# AD7173adcModule.net
KiCad netlist of a schematic drawn in Altium Designer
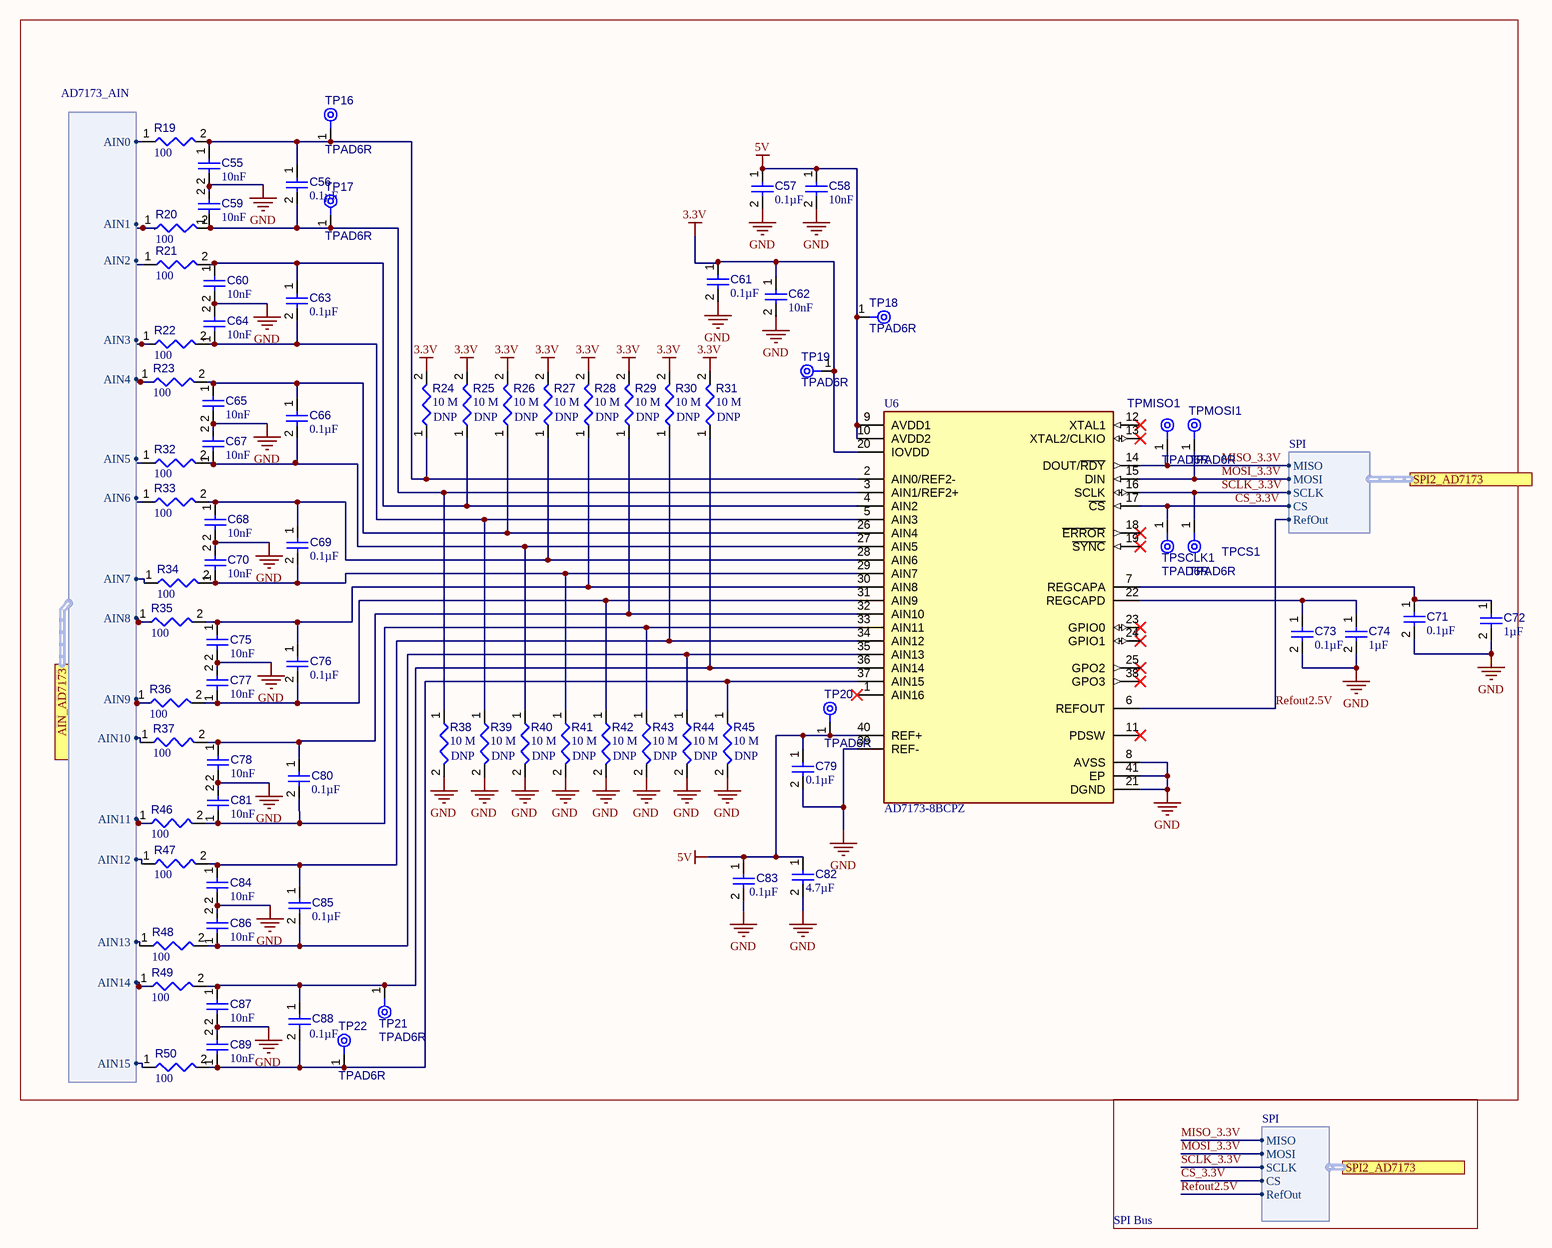
[diagram p0: AD7173adcModule.SchDoc]

(export (version "E")
  (design (tool "Eeschema 10.0.6"))
  (components
    (comp (ref "C55")
      (value "10nF")
      (footprint "CAPC1608X90X40NL10T20")
      (description "Chip Capacitor, 100 nF, +/- 10%, 50 V, 0603 (1608 Metric)")
      (fields (field (name "TOLERANCE") "10%") (field (name "Comment") "Capacitor 100 nF +/-10% 50 V 0603"))
      (libsource (lib "Gidon_Workspace") (part "CAP-NP-2"))
    )
    (comp (ref "C56")
      (value "0.1µF")
      (footprint "CAPC1608X90X40LL10T20")
      (description "Chip Capacitor, 1 uF, +/- 10%, 25 V, 0603 (1608 Metric)")
      (fields (field (name "TOLERANCE") "10%") (field (name "Comment") "Capacitor 1 uF +/- 10% 25 V 0603"))
      (libsource (lib "Gidon_Workspace") (part "CAP-NP-2"))
    )
    (comp (ref "C57")
      (value "0.1µF")
      (footprint "CAPC1608X90X40LL10T20")
      (description "Chip Capacitor, 1 uF, +/- 10%, 25 V, 0603 (1608 Metric)")
      (fields (field (name "TOLERANCE") "10%") (field (name "Comment") "Capacitor 1 uF +/- 10% 25 V 0603"))
      (libsource (lib "Gidon_Workspace") (part "CAP-NP-2"))
    )
    (comp (ref "C58")
      (value "10nF")
      (footprint "CAPC1608X90X40NL10T20")
      (description "Chip Capacitor, 100 nF, +/- 10%, 50 V, 0603 (1608 Metric)")
      (fields (field (name "TOLERANCE") "10%") (field (name "Comment") "Capacitor 100 nF +/-10% 50 V 0603"))
      (libsource (lib "Gidon_Workspace") (part "CAP-NP-2"))
    )
    (comp (ref "C59")
      (value "10nF")
      (footprint "CAPC1608X90X40NL10T20")
      (description "Chip Capacitor, 100 nF, +/- 10%, 50 V, 0603 (1608 Metric)")
      (fields (field (name "TOLERANCE") "10%") (field (name "Comment") "Capacitor 100 nF +/-10% 50 V 0603"))
      (libsource (lib "Gidon_Workspace") (part "CAP-NP-2"))
    )
    (comp (ref "C60")
      (value "10nF")
      (footprint "CAPC1608X90X40NL10T20")
      (description "Chip Capacitor, 100 nF, +/- 10%, 50 V, 0603 (1608 Metric)")
      (fields (field (name "TOLERANCE") "10%") (field (name "Comment") "Capacitor 100 nF +/-10% 50 V 0603"))
      (libsource (lib "Gidon_Workspace") (part "CAP-NP-2"))
    )
    (comp (ref "C61")
      (value "0.1µF")
      (footprint "CAPC1608X90X40LL10T20")
      (description "Chip Capacitor, 1 uF, +/- 10%, 25 V, 0603 (1608 Metric)")
      (fields (field (name "TOLERANCE") "10%") (field (name "Comment") "Capacitor 1 uF +/- 10% 25 V 0603"))
      (libsource (lib "Gidon_Workspace") (part "CAP-NP-2"))
    )
    (comp (ref "C62")
      (value "10nF")
      (footprint "CAPC1608X90X40NL10T20")
      (description "Chip Capacitor, 100 nF, +/- 10%, 50 V, 0603 (1608 Metric)")
      (fields (field (name "TOLERANCE") "10%") (field (name "Comment") "Capacitor 100 nF +/-10% 50 V 0603"))
      (libsource (lib "Gidon_Workspace") (part "CAP-NP-2"))
    )
    (comp (ref "C63")
      (value "0.1µF")
      (footprint "CAPC1608X90X40LL10T20")
      (description "Chip Capacitor, 1 uF, +/- 10%, 25 V, 0603 (1608 Metric)")
      (fields (field (name "TOLERANCE") "10%") (field (name "Comment") "Capacitor 1 uF +/- 10% 25 V 0603"))
      (libsource (lib "Gidon_Workspace") (part "CAP-NP-2"))
    )
    (comp (ref "C64")
      (value "10nF")
      (footprint "CAPC1608X90X40NL10T20")
      (description "Chip Capacitor, 100 nF, +/- 10%, 50 V, 0603 (1608 Metric)")
      (fields (field (name "TOLERANCE") "10%") (field (name "Comment") "Capacitor 100 nF +/-10% 50 V 0603"))
      (libsource (lib "Gidon_Workspace") (part "CAP-NP-2"))
    )
    (comp (ref "C65")
      (value "10nF")
      (footprint "CAPC1608X90X40NL10T20")
      (description "Chip Capacitor, 100 nF, +/- 10%, 50 V, 0603 (1608 Metric)")
      (fields (field (name "TOLERANCE") "10%") (field (name "Comment") "Capacitor 100 nF +/-10% 50 V 0603"))
      (libsource (lib "Gidon_Workspace") (part "CAP-NP-2"))
    )
    (comp (ref "C66")
      (value "0.1µF")
      (footprint "CAPC1608X90X40LL10T20")
      (description "Chip Capacitor, 1 uF, +/- 10%, 25 V, 0603 (1608 Metric)")
      (fields (field (name "TOLERANCE") "10%") (field (name "Comment") "Capacitor 1 uF +/- 10% 25 V 0603"))
      (libsource (lib "Gidon_Workspace") (part "CAP-NP-2"))
    )
    (comp (ref "C67")
      (value "10nF")
      (footprint "CAPC1608X90X40NL10T20")
      (description "Chip Capacitor, 100 nF, +/- 10%, 50 V, 0603 (1608 Metric)")
      (fields (field (name "TOLERANCE") "10%") (field (name "Comment") "Capacitor 100 nF +/-10% 50 V 0603"))
      (libsource (lib "Gidon_Workspace") (part "CAP-NP-2"))
    )
    (comp (ref "C68")
      (value "10nF")
      (footprint "CAPC1608X90X40NL10T20")
      (description "Chip Capacitor, 100 nF, +/- 10%, 50 V, 0603 (1608 Metric)")
      (fields (field (name "TOLERANCE") "10%") (field (name "Comment") "Capacitor 100 nF +/-10% 50 V 0603"))
      (libsource (lib "Gidon_Workspace") (part "CAP-NP-2"))
    )
    (comp (ref "C69")
      (value "0.1µF")
      (footprint "CAPC1608X90X40LL10T20")
      (description "Chip Capacitor, 1 uF, +/- 10%, 25 V, 0603 (1608 Metric)")
      (fields (field (name "TOLERANCE") "10%") (field (name "Comment") "Capacitor 1 uF +/- 10% 25 V 0603"))
      (libsource (lib "Gidon_Workspace") (part "CAP-NP-2"))
    )
    (comp (ref "C70")
      (value "10nF")
      (footprint "CAPC1608X90X40NL10T20")
      (description "Chip Capacitor, 100 nF, +/- 10%, 50 V, 0603 (1608 Metric)")
      (fields (field (name "TOLERANCE") "10%") (field (name "Comment") "Capacitor 100 nF +/-10% 50 V 0603"))
      (libsource (lib "Gidon_Workspace") (part "CAP-NP-2"))
    )
    (comp (ref "C71")
      (value "0.1µF")
      (footprint "CAPC1608X90X40LL10T20")
      (description "Chip Capacitor, 1 uF, +/- 10%, 25 V, 0603 (1608 Metric)")
      (fields (field (name "TOLERANCE") "10%") (field (name "Comment") "Capacitor 1 uF +/- 10% 25 V 0603"))
      (libsource (lib "Gidon_Workspace") (part "CAP-NP-2"))
    )
    (comp (ref "C72")
      (value "1µF")
      (footprint "CAPC1608X94X35NL15T15")
      (description "Chip Capacitor, 1 uF, +/- 10%, 16 V, 0603 (1608 Metric)")
      (fields (field (name "TOLERANCE") "10%") (field (name "Comment") "Capacitor 1 uF +/- 10% 16 V 0603"))
      (libsource (lib "Gidon_Workspace") (part "CAP-NP-2"))
    )
    (comp (ref "C73")
      (value "0.1µF")
      (footprint "CAPC1608X90X40LL10T20")
      (description "Chip Capacitor, 1 uF, +/- 10%, 25 V, 0603 (1608 Metric)")
      (fields (field (name "TOLERANCE") "10%") (field (name "Comment") "Capacitor 1 uF +/- 10% 25 V 0603"))
      (libsource (lib "Gidon_Workspace") (part "CAP-NP-2"))
    )
    (comp (ref "C74")
      (value "1µF")
      (footprint "CAPC1608X94X35NL15T15")
      (description "Chip Capacitor, 1 uF, +/- 10%, 16 V, 0603 (1608 Metric)")
      (fields (field (name "TOLERANCE") "10%") (field (name "Comment") "Capacitor 1 uF +/- 10% 16 V 0603"))
      (libsource (lib "Gidon_Workspace") (part "CAP-NP-2"))
    )
    (comp (ref "C75")
      (value "10nF")
      (footprint "CAPC1608X90X40NL10T20")
      (description "Chip Capacitor, 100 nF, +/- 10%, 50 V, 0603 (1608 Metric)")
      (fields (field (name "TOLERANCE") "10%") (field (name "Comment") "Capacitor 100 nF +/-10% 50 V 0603"))
      (libsource (lib "Gidon_Workspace") (part "CAP-NP-2"))
    )
    (comp (ref "C76")
      (value "0.1µF")
      (footprint "CAPC1608X90X40LL10T20")
      (description "Chip Capacitor, 1 uF, +/- 10%, 25 V, 0603 (1608 Metric)")
      (fields (field (name "TOLERANCE") "10%") (field (name "Comment") "Capacitor 1 uF +/- 10% 25 V 0603"))
      (libsource (lib "Gidon_Workspace") (part "CAP-NP-2"))
    )
    (comp (ref "C77")
      (value "10nF")
      (footprint "CAPC1608X90X40NL10T20")
      (description "Chip Capacitor, 100 nF, +/- 10%, 50 V, 0603 (1608 Metric)")
      (fields (field (name "TOLERANCE") "10%") (field (name "Comment") "Capacitor 100 nF +/-10% 50 V 0603"))
      (libsource (lib "Gidon_Workspace") (part "CAP-NP-2"))
    )
    (comp (ref "C78")
      (value "10nF")
      (footprint "CAPC1608X90X40NL10T20")
      (description "Chip Capacitor, 100 nF, +/- 10%, 50 V, 0603 (1608 Metric)")
      (fields (field (name "TOLERANCE") "10%") (field (name "Comment") "Capacitor 100 nF +/-10% 50 V 0603"))
      (libsource (lib "Gidon_Workspace") (part "CAP-NP-2"))
    )
    (comp (ref "C79")
      (value "0.1µF")
      (footprint "CAPC1608X90X40LL10T20")
      (description "Chip Capacitor, 1 uF, +/- 10%, 25 V, 0603 (1608 Metric)")
      (fields (field (name "TOLERANCE") "10%") (field (name "Comment") "Capacitor 1 uF +/- 10% 25 V 0603"))
      (libsource (lib "Gidon_Workspace") (part "CAP-NP-2"))
    )
    (comp (ref "C80")
      (value "0.1µF")
      (footprint "CAPC1608X90X40LL10T20")
      (description "Chip Capacitor, 1 uF, +/- 10%, 25 V, 0603 (1608 Metric)")
      (fields (field (name "TOLERANCE") "10%") (field (name "Comment") "Capacitor 1 uF +/- 10% 25 V 0603"))
      (libsource (lib "Gidon_Workspace") (part "CAP-NP-2"))
    )
    (comp (ref "C81")
      (value "10nF")
      (footprint "CAPC1608X90X40NL10T20")
      (description "Chip Capacitor, 100 nF, +/- 10%, 50 V, 0603 (1608 Metric)")
      (fields (field (name "TOLERANCE") "10%") (field (name "Comment") "Capacitor 100 nF +/-10% 50 V 0603"))
      (libsource (lib "Gidon_Workspace") (part "CAP-NP-2"))
    )
    (comp (ref "C82")
      (value "4.7µF")
      (footprint "CAPC0603(1608)100_L")
      (description "Chip Capacitor, 4.7µF +/-20%, 10V, 0603, Thickness 1 mm")
      (fields (field (name "TOLERANCE") "10%") (field (name "Comment") "Capacitor 4.7µF +/-20% 10V 0603"))
      (libsource (lib "Gidon_Workspace") (part "CAP-NP-2"))
    )
    (comp (ref "C83")
      (value "0.1µF")
      (footprint "CAPC1608X90X40LL10T20")
      (description "Chip Capacitor, 1 uF, +/- 10%, 25 V, 0603 (1608 Metric)")
      (fields (field (name "TOLERANCE") "10%") (field (name "Comment") "Capacitor 1 uF +/- 10% 25 V 0603"))
      (libsource (lib "Gidon_Workspace") (part "CAP-NP-2"))
    )
    (comp (ref "C84")
      (value "10nF")
      (footprint "CAPC1608X90X40NL10T20")
      (description "Chip Capacitor, 100 nF, +/- 10%, 50 V, 0603 (1608 Metric)")
      (fields (field (name "TOLERANCE") "10%") (field (name "Comment") "Capacitor 100 nF +/-10% 50 V 0603"))
      (libsource (lib "Gidon_Workspace") (part "CAP-NP-2"))
    )
    (comp (ref "C85")
      (value "0.1µF")
      (footprint "CAPC1608X90X40LL10T20")
      (description "Chip Capacitor, 1 uF, +/- 10%, 25 V, 0603 (1608 Metric)")
      (fields (field (name "TOLERANCE") "10%") (field (name "Comment") "Capacitor 1 uF +/- 10% 25 V 0603"))
      (libsource (lib "Gidon_Workspace") (part "CAP-NP-2"))
    )
    (comp (ref "C86")
      (value "10nF")
      (footprint "CAPC1608X90X40NL10T20")
      (description "Chip Capacitor, 100 nF, +/- 10%, 50 V, 0603 (1608 Metric)")
      (fields (field (name "TOLERANCE") "10%") (field (name "Comment") "Capacitor 100 nF +/-10% 50 V 0603"))
      (libsource (lib "Gidon_Workspace") (part "CAP-NP-2"))
    )
    (comp (ref "C87")
      (value "10nF")
      (footprint "CAPC1608X90X40NL10T20")
      (description "Chip Capacitor, 100 nF, +/- 10%, 50 V, 0603 (1608 Metric)")
      (fields (field (name "TOLERANCE") "10%") (field (name "Comment") "Capacitor 100 nF +/-10% 50 V 0603"))
      (libsource (lib "Gidon_Workspace") (part "CAP-NP-2"))
    )
    (comp (ref "C88")
      (value "0.1µF")
      (footprint "CAPC1608X90X40LL10T20")
      (description "Chip Capacitor, 1 uF, +/- 10%, 25 V, 0603 (1608 Metric)")
      (fields (field (name "TOLERANCE") "10%") (field (name "Comment") "Capacitor 1 uF +/- 10% 25 V 0603"))
      (libsource (lib "Gidon_Workspace") (part "CAP-NP-2"))
    )
    (comp (ref "C89")
      (value "10nF")
      (footprint "CAPC1608X90X40NL10T20")
      (description "Chip Capacitor, 100 nF, +/- 10%, 50 V, 0603 (1608 Metric)")
      (fields (field (name "TOLERANCE") "10%") (field (name "Comment") "Capacitor 100 nF +/-10% 50 V 0603"))
      (libsource (lib "Gidon_Workspace") (part "CAP-NP-2"))
    )
    (comp (ref "R19")
      (value "100")
      (footprint "RESC0603(1608)_L")
      (description "Chip Resistor, 120 Ohms, +/-5 %, 0.1 W, -55 to 155 degC, 0603")
      (fields (field (name "POWER") "100mW") (field (name "TOLERANCE") "5%"))
      (libsource (lib "Gidon_Workspace") (part "RES-2"))
    )
    (comp (ref "R20")
      (value "100")
      (footprint "RESC0603(1608)_L")
      (description "Chip Resistor, 120 Ohms, +/-5 %, 0.1 W, -55 to 155 degC, 0603")
      (fields (field (name "POWER") "100mW") (field (name "TOLERANCE") "5%"))
      (libsource (lib "Gidon_Workspace") (part "RES-2"))
    )
    (comp (ref "R21")
      (value "100")
      (footprint "RESC0603(1608)_L")
      (description "Chip Resistor, 120 Ohms, +/-5 %, 0.1 W, -55 to 155 degC, 0603")
      (fields (field (name "POWER") "100mW") (field (name "TOLERANCE") "5%"))
      (libsource (lib "Gidon_Workspace") (part "RES-2"))
    )
    (comp (ref "R22")
      (value "100")
      (footprint "RESC0603(1608)_L")
      (description "Chip Resistor, 120 Ohms, +/-5 %, 0.1 W, -55 to 155 degC, 0603")
      (fields (field (name "POWER") "100mW") (field (name "TOLERANCE") "5%"))
      (libsource (lib "Gidon_Workspace") (part "RES-2"))
    )
    (comp (ref "R23")
      (value "100")
      (footprint "RESC0603(1608)_L")
      (description "Chip Resistor, 120 Ohms, +/-5 %, 0.1 W, -55 to 155 degC, 0603")
      (fields (field (name "POWER") "100mW") (field (name "TOLERANCE") "5%"))
      (libsource (lib "Gidon_Workspace") (part "RES-2"))
    )
    (comp (ref "R24")
      (value "10 M")
      (footprint "RESC0603(1608)_L")
      (description "Chip Resistor, 120 Ohms, +/-5 %, 0.1 W, -55 to 155 degC, 0603")
      (fields (field (name "POWER") "100mW") (field (name "TOLERANCE") "5%"))
      (libsource (lib "Gidon_Workspace") (part "RES-2"))
    )
    (comp (ref "R25")
      (value "10 M")
      (footprint "RESC0603(1608)_L")
      (description "Chip Resistor, 120 Ohms, +/-5 %, 0.1 W, -55 to 155 degC, 0603")
      (fields (field (name "POWER") "100mW") (field (name "TOLERANCE") "5%"))
      (libsource (lib "Gidon_Workspace") (part "RES-2"))
    )
    (comp (ref "R26")
      (value "10 M")
      (footprint "RESC0603(1608)_L")
      (description "Chip Resistor, 120 Ohms, +/-5 %, 0.1 W, -55 to 155 degC, 0603")
      (fields (field (name "POWER") "100mW") (field (name "TOLERANCE") "5%"))
      (libsource (lib "Gidon_Workspace") (part "RES-2"))
    )
    (comp (ref "R27")
      (value "10 M")
      (footprint "RESC0603(1608)_L")
      (description "Chip Resistor, 120 Ohms, +/-5 %, 0.1 W, -55 to 155 degC, 0603")
      (fields (field (name "POWER") "100mW") (field (name "TOLERANCE") "5%"))
      (libsource (lib "Gidon_Workspace") (part "RES-2"))
    )
    (comp (ref "R28")
      (value "10 M")
      (footprint "RESC0603(1608)_L")
      (description "Chip Resistor, 120 Ohms, +/-5 %, 0.1 W, -55 to 155 degC, 0603")
      (fields (field (name "POWER") "100mW") (field (name "TOLERANCE") "5%"))
      (libsource (lib "Gidon_Workspace") (part "RES-2"))
    )
    (comp (ref "R29")
      (value "10 M")
      (footprint "RESC0603(1608)_L")
      (description "Chip Resistor, 120 Ohms, +/-5 %, 0.1 W, -55 to 155 degC, 0603")
      (fields (field (name "POWER") "100mW") (field (name "TOLERANCE") "5%"))
      (libsource (lib "Gidon_Workspace") (part "RES-2"))
    )
    (comp (ref "R30")
      (value "10 M")
      (footprint "RESC0603(1608)_L")
      (description "Chip Resistor, 120 Ohms, +/-5 %, 0.1 W, -55 to 155 degC, 0603")
      (fields (field (name "POWER") "100mW") (field (name "TOLERANCE") "5%"))
      (libsource (lib "Gidon_Workspace") (part "RES-2"))
    )
    (comp (ref "R31")
      (value "10 M")
      (footprint "RESC0603(1608)_L")
      (description "Chip Resistor, 120 Ohms, +/-5 %, 0.1 W, -55 to 155 degC, 0603")
      (fields (field (name "POWER") "100mW") (field (name "TOLERANCE") "5%"))
      (libsource (lib "Gidon_Workspace") (part "RES-2"))
    )
    (comp (ref "R32")
      (value "100")
      (footprint "RESC0603(1608)_L")
      (description "Chip Resistor, 120 Ohms, +/-5 %, 0.1 W, -55 to 155 degC, 0603")
      (fields (field (name "POWER") "100mW") (field (name "TOLERANCE") "5%"))
      (libsource (lib "Gidon_Workspace") (part "RES-2"))
    )
    (comp (ref "R33")
      (value "100")
      (footprint "RESC0603(1608)_L")
      (description "Chip Resistor, 120 Ohms, +/-5 %, 0.1 W, -55 to 155 degC, 0603")
      (fields (field (name "POWER") "100mW") (field (name "TOLERANCE") "5%"))
      (libsource (lib "Gidon_Workspace") (part "RES-2"))
    )
    (comp (ref "R34")
      (value "100")
      (footprint "RESC0603(1608)_L")
      (description "Chip Resistor, 120 Ohms, +/-5 %, 0.1 W, -55 to 155 degC, 0603")
      (fields (field (name "POWER") "100mW") (field (name "TOLERANCE") "5%"))
      (libsource (lib "Gidon_Workspace") (part "RES-2"))
    )
    (comp (ref "R35")
      (value "100")
      (footprint "RESC0603(1608)_L")
      (description "Chip Resistor, 120 Ohms, +/-5 %, 0.1 W, -55 to 155 degC, 0603")
      (fields (field (name "POWER") "100mW") (field (name "TOLERANCE") "5%"))
      (libsource (lib "Gidon_Workspace") (part "RES-2"))
    )
    (comp (ref "R36")
      (value "100")
      (footprint "RESC0603(1608)_L")
      (description "Chip Resistor, 120 Ohms, +/-5 %, 0.1 W, -55 to 155 degC, 0603")
      (fields (field (name "POWER") "100mW") (field (name "TOLERANCE") "5%"))
      (libsource (lib "Gidon_Workspace") (part "RES-2"))
    )
    (comp (ref "R37")
      (value "100")
      (footprint "RESC0603(1608)_L")
      (description "Chip Resistor, 120 Ohms, +/-5 %, 0.1 W, -55 to 155 degC, 0603")
      (fields (field (name "POWER") "100mW") (field (name "TOLERANCE") "5%"))
      (libsource (lib "Gidon_Workspace") (part "RES-2"))
    )
    (comp (ref "R38")
      (value "10 M")
      (footprint "RESC0603(1608)_L")
      (description "Chip Resistor, 120 Ohms, +/-5 %, 0.1 W, -55 to 155 degC, 0603")
      (fields (field (name "POWER") "100mW") (field (name "TOLERANCE") "5%"))
      (libsource (lib "Gidon_Workspace") (part "RES-2"))
    )
    (comp (ref "R39")
      (value "10 M")
      (footprint "RESC0603(1608)_L")
      (description "Chip Resistor, 120 Ohms, +/-5 %, 0.1 W, -55 to 155 degC, 0603")
      (fields (field (name "POWER") "100mW") (field (name "TOLERANCE") "5%"))
      (libsource (lib "Gidon_Workspace") (part "RES-2"))
    )
    (comp (ref "R40")
      (value "10 M")
      (footprint "RESC0603(1608)_L")
      (description "Chip Resistor, 120 Ohms, +/-5 %, 0.1 W, -55 to 155 degC, 0603")
      (fields (field (name "POWER") "100mW") (field (name "TOLERANCE") "5%"))
      (libsource (lib "Gidon_Workspace") (part "RES-2"))
    )
    (comp (ref "R41")
      (value "10 M")
      (footprint "RESC0603(1608)_L")
      (description "Chip Resistor, 120 Ohms, +/-5 %, 0.1 W, -55 to 155 degC, 0603")
      (fields (field (name "POWER") "100mW") (field (name "TOLERANCE") "5%"))
      (libsource (lib "Gidon_Workspace") (part "RES-2"))
    )
    (comp (ref "R42")
      (value "10 M")
      (footprint "RESC0603(1608)_L")
      (description "Chip Resistor, 120 Ohms, +/-5 %, 0.1 W, -55 to 155 degC, 0603")
      (fields (field (name "POWER") "100mW") (field (name "TOLERANCE") "5%"))
      (libsource (lib "Gidon_Workspace") (part "RES-2"))
    )
    (comp (ref "R43")
      (value "10 M")
      (footprint "RESC0603(1608)_L")
      (description "Chip Resistor, 120 Ohms, +/-5 %, 0.1 W, -55 to 155 degC, 0603")
      (fields (field (name "POWER") "100mW") (field (name "TOLERANCE") "5%"))
      (libsource (lib "Gidon_Workspace") (part "RES-2"))
    )
    (comp (ref "R44")
      (value "10 M")
      (footprint "RESC0603(1608)_L")
      (description "Chip Resistor, 120 Ohms, +/-5 %, 0.1 W, -55 to 155 degC, 0603")
      (fields (field (name "POWER") "100mW") (field (name "TOLERANCE") "5%"))
      (libsource (lib "Gidon_Workspace") (part "RES-2"))
    )
    (comp (ref "R45")
      (value "10 M")
      (footprint "RESC0603(1608)_L")
      (description "Chip Resistor, 120 Ohms, +/-5 %, 0.1 W, -55 to 155 degC, 0603")
      (fields (field (name "POWER") "100mW") (field (name "TOLERANCE") "5%"))
      (libsource (lib "Gidon_Workspace") (part "RES-2"))
    )
    (comp (ref "R46")
      (value "100")
      (footprint "RESC0603(1608)_L")
      (description "Chip Resistor, 120 Ohms, +/-5 %, 0.1 W, -55 to 155 degC, 0603")
      (fields (field (name "POWER") "100mW") (field (name "TOLERANCE") "5%"))
      (libsource (lib "Gidon_Workspace") (part "RES-2"))
    )
    (comp (ref "R47")
      (value "100")
      (footprint "RESC0603(1608)_L")
      (description "Chip Resistor, 120 Ohms, +/-5 %, 0.1 W, -55 to 155 degC, 0603")
      (fields (field (name "POWER") "100mW") (field (name "TOLERANCE") "5%"))
      (libsource (lib "Gidon_Workspace") (part "RES-2"))
    )
    (comp (ref "R48")
      (value "100")
      (footprint "RESC0603(1608)_L")
      (description "Chip Resistor, 120 Ohms, +/-5 %, 0.1 W, -55 to 155 degC, 0603")
      (fields (field (name "POWER") "100mW") (field (name "TOLERANCE") "5%"))
      (libsource (lib "Gidon_Workspace") (part "RES-2"))
    )
    (comp (ref "R49")
      (value "100")
      (footprint "RESC0603(1608)_L")
      (description "Chip Resistor, 120 Ohms, +/-5 %, 0.1 W, -55 to 155 degC, 0603")
      (fields (field (name "POWER") "100mW") (field (name "TOLERANCE") "5%"))
      (libsource (lib "Gidon_Workspace") (part "RES-2"))
    )
    (comp (ref "R50")
      (value "100")
      (footprint "RESC0603(1608)_L")
      (description "Chip Resistor, 120 Ohms, +/-5 %, 0.1 W, -55 to 155 degC, 0603")
      (fields (field (name "POWER") "100mW") (field (name "TOLERANCE") "5%"))
      (libsource (lib "Gidon_Workspace") (part "RES-2"))
    )
    (comp (ref "TP16")
      (value "TPAD6R")
      (footprint "TP06R")
      (description "0.6mm round")
      (libsource (lib "Yuxuan chen") (part "CMP-001-0001-4"))
    )
    (comp (ref "TP17")
      (value "TPAD6R")
      (footprint "TP06R")
      (description "0.6mm round")
      (libsource (lib "Yuxuan chen") (part "CMP-001-0001-4"))
    )
    (comp (ref "TP18")
      (value "TPAD6R")
      (footprint "TP06R")
      (description "0.6mm round")
      (libsource (lib "Yuxuan chen") (part "CMP-001-0001-4"))
    )
    (comp (ref "TP19")
      (value "TPAD6R")
      (footprint "TP06R")
      (description "0.6mm round")
      (libsource (lib "Yuxuan chen") (part "CMP-001-0001-4"))
    )
    (comp (ref "TP20")
      (value "TPAD6R")
      (footprint "TP06R")
      (description "0.6mm round")
      (libsource (lib "Yuxuan chen") (part "CMP-001-0001-4"))
    )
    (comp (ref "TP21")
      (value "TPAD6R")
      (footprint "TP06R")
      (description "0.6mm round")
      (libsource (lib "Yuxuan chen") (part "CMP-001-0001-4"))
    )
    (comp (ref "TP22")
      (value "TPAD6R")
      (footprint "TP06R")
      (description "0.6mm round")
      (libsource (lib "Yuxuan chen") (part "CMP-001-0001-4"))
    )
    (comp (ref "TPCS1")
      (value "TPAD6R")
      (footprint "TP06R")
      (description "0.6mm round")
      (libsource (lib "Yuxuan chen") (part "CMP-001-0001-4"))
    )
    (comp (ref "TPMISO1")
      (value "TPAD6R")
      (footprint "TP06R")
      (description "0.6mm round")
      (libsource (lib "Yuxuan chen") (part "CMP-001-0001-4"))
    )
    (comp (ref "TPMOSI1")
      (value "TPAD6R")
      (footprint "TP06R")
      (description "0.6mm round")
      (libsource (lib "Yuxuan chen") (part "CMP-001-0001-4"))
    )
    (comp (ref "TPSCLK1")
      (value "TPAD6R")
      (footprint "TP06R")
      (description "0.6mm round")
      (libsource (lib "Yuxuan chen") (part "CMP-001-0001-4"))
    )
    (comp (ref "U6")
      (value "AD7173-8BCPZ")
      (footprint "FP-CP-40-14-IPC_C")
      (description "IC ADC 24BIT SIGMA-DELTA 40LFCSP")
      (libsource (lib "Altium Content Vault") (part "710051527f613229cb63325670d736c"))
    )
  )
  (nets
    (net (code "3") (name "/AIN0") (class "Default")
      (node (ref "R19") (pin "1") (pinfunction "1_1") (pintype "passive"))
    )
    (net (code "4") (name "/AIN1") (class "Default")
      (node (ref "R20") (pin "1") (pinfunction "1_1") (pintype "passive"))
    )
    (net (code "5") (name "/AIN2") (class "Default")
      (node (ref "R21") (pin "1") (pinfunction "1_1") (pintype "passive"))
    )
    (net (code "6") (name "/AIN3") (class "Default")
      (node (ref "R22") (pin "1") (pinfunction "1_1") (pintype "passive"))
    )
    (net (code "7") (name "/AIN4") (class "Default")
      (node (ref "R23") (pin "1") (pinfunction "1_1") (pintype "passive"))
    )
    (net (code "8") (name "/AIN5") (class "Default")
      (node (ref "R32") (pin "1") (pinfunction "1_1") (pintype "passive"))
    )
    (net (code "9") (name "/AIN6") (class "Default")
      (node (ref "R33") (pin "1") (pinfunction "1_1") (pintype "passive"))
    )
    (net (code "10") (name "/AIN7") (class "Default")
      (node (ref "R34") (pin "1") (pinfunction "1_1") (pintype "passive"))
    )
    (net (code "11") (name "/AIN8") (class "Default")
      (node (ref "R35") (pin "1") (pinfunction "1_1") (pintype "passive"))
    )
    (net (code "12") (name "/AIN9") (class "Default")
      (node (ref "R36") (pin "1") (pinfunction "1_1") (pintype "passive"))
    )
    (net (code "13") (name "/AIN10") (class "Default")
      (node (ref "R37") (pin "1") (pinfunction "1_1") (pintype "passive"))
    )
    (net (code "14") (name "/AIN11") (class "Default")
      (node (ref "R46") (pin "1") (pinfunction "1_1") (pintype "passive"))
    )
    (net (code "15") (name "/AIN12") (class "Default")
      (node (ref "R47") (pin "1") (pinfunction "1_1") (pintype "passive"))
    )
    (net (code "16") (name "/AIN13") (class "Default")
      (node (ref "R48") (pin "1") (pinfunction "1_1") (pintype "passive"))
    )
    (net (code "17") (name "/AIN14") (class "Default")
      (node (ref "R49") (pin "1") (pinfunction "1_1") (pintype "passive"))
    )
    (net (code "18") (name "/AIN15") (class "Default")
      (node (ref "R50") (pin "1") (pinfunction "1_1") (pintype "passive"))
    )
    (net (code "19") (name "/CS_3.3V") (class "Default")
      (node (ref "TPSCLK1") (pin "1") (pinfunction "TP_1") (pintype "passive"))
      (node (ref "U6") (pin "17") (pinfunction "~{CS}_17") (pintype "input"))
    )
    (net (code "20") (name "/MISO_3.3V") (class "Default")
      (node (ref "TPMISO1") (pin "1") (pinfunction "TP_1") (pintype "passive"))
      (node (ref "U6") (pin "14") (pinfunction "DOUT/~{RDY}_14") (pintype "output"))
    )
    (net (code "21") (name "/MOSI_3.3V") (class "Default")
      (node (ref "TPMOSI1") (pin "1") (pinfunction "TP_1") (pintype "passive"))
      (node (ref "U6") (pin "15") (pinfunction "DIN_15") (pintype "input"))
    )
    (net (code "22") (name "/Refout2.5V") (class "Default")
      (node (ref "U6") (pin "6") (pinfunction "REFOUT_6") (pintype "passive"))
    )
    (net (code "23") (name "/SCLK_3.3V") (class "Default")
      (node (ref "TPCS1") (pin "1") (pinfunction "TP_1") (pintype "passive"))
      (node (ref "U6") (pin "16") (pinfunction "SCLK_16") (pintype "bidirectional"))
    )
    (net (code "26") (name "3.3V") (class "Default")
      (node (ref "C61") (pin "1") (pinfunction "1_1") (pintype "passive"))
      (node (ref "C62") (pin "1") (pinfunction "1_1") (pintype "passive"))
      (node (ref "R24") (pin "2") (pinfunction "2_2") (pintype "passive"))
      (node (ref "R25") (pin "2") (pinfunction "2_2") (pintype "passive"))
      (node (ref "R26") (pin "2") (pinfunction "2_2") (pintype "passive"))
      (node (ref "R27") (pin "2") (pinfunction "2_2") (pintype "passive"))
      (node (ref "R28") (pin "2") (pinfunction "2_2") (pintype "passive"))
      (node (ref "R29") (pin "2") (pinfunction "2_2") (pintype "passive"))
      (node (ref "R30") (pin "2") (pinfunction "2_2") (pintype "passive"))
      (node (ref "R31") (pin "2") (pinfunction "2_2") (pintype "passive"))
      (node (ref "TP19") (pin "1") (pinfunction "TP_1") (pintype "passive"))
      (node (ref "U6") (pin "20") (pinfunction "IOVDD_20") (pintype "power_in"))
    )
    (net (code "27") (name "5V") (class "Default")
      (node (ref "C57") (pin "1") (pinfunction "1_1") (pintype "passive"))
      (node (ref "C58") (pin "1") (pinfunction "1_1") (pintype "passive"))
      (node (ref "C79") (pin "1") (pinfunction "1_1") (pintype "passive"))
      (node (ref "C82") (pin "1") (pinfunction "1_1") (pintype "passive"))
      (node (ref "C83") (pin "1") (pinfunction "1_1") (pintype "passive"))
      (node (ref "TP18") (pin "1") (pinfunction "TP_1") (pintype "passive"))
      (node (ref "TP20") (pin "1") (pinfunction "TP_1") (pintype "passive"))
      (node (ref "U6") (pin "10") (pinfunction "AVDD2_10") (pintype "power_in"))
      (node (ref "U6") (pin "40") (pinfunction "REF+_40") (pintype "passive"))
      (node (ref "U6") (pin "9") (pinfunction "AVDD1_9") (pintype "power_in"))
    )
    (net (code "28") (name "GND") (class "Default")
      (node (ref "C55") (pin "2") (pinfunction "2_2") (pintype "passive"))
      (node (ref "C57") (pin "2") (pinfunction "2_2") (pintype "passive"))
      (node (ref "C58") (pin "2") (pinfunction "2_2") (pintype "passive"))
      (node (ref "C59") (pin "2") (pinfunction "2_2") (pintype "passive"))
      (node (ref "C60") (pin "2") (pinfunction "2_2") (pintype "passive"))
      (node (ref "C61") (pin "2") (pinfunction "2_2") (pintype "passive"))
      (node (ref "C62") (pin "2") (pinfunction "2_2") (pintype "passive"))
      (node (ref "C64") (pin "2") (pinfunction "2_2") (pintype "passive"))
      (node (ref "C65") (pin "2") (pinfunction "2_2") (pintype "passive"))
      (node (ref "C67") (pin "2") (pinfunction "2_2") (pintype "passive"))
      (node (ref "C68") (pin "2") (pinfunction "2_2") (pintype "passive"))
      (node (ref "C70") (pin "2") (pinfunction "2_2") (pintype "passive"))
      (node (ref "C71") (pin "2") (pinfunction "2_2") (pintype "passive"))
      (node (ref "C72") (pin "2") (pinfunction "2_2") (pintype "passive"))
      (node (ref "C73") (pin "2") (pinfunction "2_2") (pintype "passive"))
      (node (ref "C74") (pin "2") (pinfunction "2_2") (pintype "passive"))
      (node (ref "C75") (pin "2") (pinfunction "2_2") (pintype "passive"))
      (node (ref "C77") (pin "2") (pinfunction "2_2") (pintype "passive"))
      (node (ref "C78") (pin "2") (pinfunction "2_2") (pintype "passive"))
      (node (ref "C79") (pin "2") (pinfunction "2_2") (pintype "passive"))
      (node (ref "C81") (pin "2") (pinfunction "2_2") (pintype "passive"))
      (node (ref "C82") (pin "2") (pinfunction "2_2") (pintype "passive"))
      (node (ref "C83") (pin "2") (pinfunction "2_2") (pintype "passive"))
      (node (ref "C84") (pin "2") (pinfunction "2_2") (pintype "passive"))
      (node (ref "C86") (pin "2") (pinfunction "2_2") (pintype "passive"))
      (node (ref "C87") (pin "2") (pinfunction "2_2") (pintype "passive"))
      (node (ref "C89") (pin "2") (pinfunction "2_2") (pintype "passive"))
      (node (ref "R38") (pin "2") (pinfunction "2_2") (pintype "passive"))
      (node (ref "R39") (pin "2") (pinfunction "2_2") (pintype "passive"))
      (node (ref "R40") (pin "2") (pinfunction "2_2") (pintype "passive"))
      (node (ref "R41") (pin "2") (pinfunction "2_2") (pintype "passive"))
      (node (ref "R42") (pin "2") (pinfunction "2_2") (pintype "passive"))
      (node (ref "R43") (pin "2") (pinfunction "2_2") (pintype "passive"))
      (node (ref "R44") (pin "2") (pinfunction "2_2") (pintype "passive"))
      (node (ref "R45") (pin "2") (pinfunction "2_2") (pintype "passive"))
      (node (ref "U6") (pin "21") (pinfunction "DGND_21") (pintype "power_in"))
      (node (ref "U6") (pin "39") (pinfunction "REF-_39") (pintype "passive"))
      (node (ref "U6") (pin "41") (pinfunction "EP_41") (pintype "passive"))
      (node (ref "U6") (pin "8") (pinfunction "AVSS_8") (pintype "power_in"))
    )
    (net (code "29") (name "Net-(TP16-TP)") (class "Default")
      (node (ref "C55") (pin "1") (pinfunction "1_1") (pintype "passive"))
      (node (ref "C56") (pin "1") (pinfunction "1_1") (pintype "passive"))
      (node (ref "R19") (pin "2") (pinfunction "2_2") (pintype "passive"))
      (node (ref "R24") (pin "1") (pinfunction "1_1") (pintype "passive"))
      (node (ref "TP16") (pin "1") (pinfunction "TP_1") (pintype "passive"))
      (node (ref "U6") (pin "2") (pinfunction "AIN0/REF2-_2") (pintype "passive"))
    )
    (net (code "30") (name "Net-(TP17-TP)") (class "Default")
      (node (ref "C56") (pin "2") (pinfunction "2_2") (pintype "passive"))
      (node (ref "C59") (pin "1") (pinfunction "1_1") (pintype "passive"))
      (node (ref "R20") (pin "2") (pinfunction "2_2") (pintype "passive"))
      (node (ref "R38") (pin "1") (pinfunction "1_1") (pintype "passive"))
      (node (ref "TP17") (pin "1") (pinfunction "TP_1") (pintype "passive"))
      (node (ref "U6") (pin "3") (pinfunction "AIN1/REF2+_3") (pintype "passive"))
    )
    (net (code "31") (name "Net-(TP21-TP)") (class "Default")
      (node (ref "C87") (pin "1") (pinfunction "1_1") (pintype "passive"))
      (node (ref "C88") (pin "1") (pinfunction "1_1") (pintype "passive"))
      (node (ref "R31") (pin "1") (pinfunction "1_1") (pintype "passive"))
      (node (ref "R49") (pin "2") (pinfunction "2_2") (pintype "passive"))
      (node (ref "TP21") (pin "1") (pinfunction "TP_1") (pintype "passive"))
      (node (ref "U6") (pin "36") (pinfunction "AIN14_36") (pintype "passive"))
    )
    (net (code "32") (name "Net-(TP22-TP)") (class "Default")
      (node (ref "C88") (pin "2") (pinfunction "2_2") (pintype "passive"))
      (node (ref "C89") (pin "1") (pinfunction "1_1") (pintype "passive"))
      (node (ref "R45") (pin "1") (pinfunction "1_1") (pintype "passive"))
      (node (ref "R50") (pin "2") (pinfunction "2_2") (pintype "passive"))
      (node (ref "TP22") (pin "1") (pinfunction "TP_1") (pintype "passive"))
      (node (ref "U6") (pin "37") (pinfunction "AIN15_37") (pintype "passive"))
    )
    (net (code "33") (name "Net-(U6-AIN2)") (class "Default")
      (node (ref "C60") (pin "1") (pinfunction "1_1") (pintype "passive"))
      (node (ref "C63") (pin "1") (pinfunction "1_1") (pintype "passive"))
      (node (ref "R21") (pin "2") (pinfunction "2_2") (pintype "passive"))
      (node (ref "R25") (pin "1") (pinfunction "1_1") (pintype "passive"))
      (node (ref "U6") (pin "4") (pinfunction "AIN2_4") (pintype "passive"))
    )
    (net (code "34") (name "Net-(U6-AIN3)") (class "Default")
      (node (ref "C63") (pin "2") (pinfunction "2_2") (pintype "passive"))
      (node (ref "C64") (pin "1") (pinfunction "1_1") (pintype "passive"))
      (node (ref "R22") (pin "2") (pinfunction "2_2") (pintype "passive"))
      (node (ref "R39") (pin "1") (pinfunction "1_1") (pintype "passive"))
      (node (ref "U6") (pin "5") (pinfunction "AIN3_5") (pintype "passive"))
    )
    (net (code "35") (name "Net-(U6-AIN4)") (class "Default")
      (node (ref "C65") (pin "1") (pinfunction "1_1") (pintype "passive"))
      (node (ref "C66") (pin "1") (pinfunction "1_1") (pintype "passive"))
      (node (ref "R23") (pin "2") (pinfunction "2_2") (pintype "passive"))
      (node (ref "R26") (pin "1") (pinfunction "1_1") (pintype "passive"))
      (node (ref "U6") (pin "26") (pinfunction "AIN4_26") (pintype "passive"))
    )
    (net (code "36") (name "Net-(U6-AIN5)") (class "Default")
      (node (ref "C66") (pin "2") (pinfunction "2_2") (pintype "passive"))
      (node (ref "C67") (pin "1") (pinfunction "1_1") (pintype "passive"))
      (node (ref "R32") (pin "2") (pinfunction "2_2") (pintype "passive"))
      (node (ref "R40") (pin "1") (pinfunction "1_1") (pintype "passive"))
      (node (ref "U6") (pin "27") (pinfunction "AIN5_27") (pintype "passive"))
    )
    (net (code "37") (name "Net-(U6-AIN6)") (class "Default")
      (node (ref "C68") (pin "1") (pinfunction "1_1") (pintype "passive"))
      (node (ref "C69") (pin "1") (pinfunction "1_1") (pintype "passive"))
      (node (ref "R27") (pin "1") (pinfunction "1_1") (pintype "passive"))
      (node (ref "R33") (pin "2") (pinfunction "2_2") (pintype "passive"))
      (node (ref "U6") (pin "28") (pinfunction "AIN6_28") (pintype "passive"))
    )
    (net (code "38") (name "Net-(U6-AIN7)") (class "Default")
      (node (ref "C69") (pin "2") (pinfunction "2_2") (pintype "passive"))
      (node (ref "C70") (pin "1") (pinfunction "1_1") (pintype "passive"))
      (node (ref "R34") (pin "2") (pinfunction "2_2") (pintype "passive"))
      (node (ref "R41") (pin "1") (pinfunction "1_1") (pintype "passive"))
      (node (ref "U6") (pin "29") (pinfunction "AIN7_29") (pintype "passive"))
    )
    (net (code "39") (name "Net-(U6-AIN8)") (class "Default")
      (node (ref "C75") (pin "1") (pinfunction "1_1") (pintype "passive"))
      (node (ref "C76") (pin "1") (pinfunction "1_1") (pintype "passive"))
      (node (ref "R28") (pin "1") (pinfunction "1_1") (pintype "passive"))
      (node (ref "R35") (pin "2") (pinfunction "2_2") (pintype "passive"))
      (node (ref "U6") (pin "30") (pinfunction "AIN8_30") (pintype "passive"))
    )
    (net (code "40") (name "Net-(U6-AIN9)") (class "Default")
      (node (ref "C76") (pin "2") (pinfunction "2_2") (pintype "passive"))
      (node (ref "C77") (pin "1") (pinfunction "1_1") (pintype "passive"))
      (node (ref "R36") (pin "2") (pinfunction "2_2") (pintype "passive"))
      (node (ref "R42") (pin "1") (pinfunction "1_1") (pintype "passive"))
      (node (ref "U6") (pin "31") (pinfunction "AIN9_31") (pintype "passive"))
    )
    (net (code "41") (name "Net-(U6-AIN10)") (class "Default")
      (node (ref "C78") (pin "1") (pinfunction "1_1") (pintype "passive"))
      (node (ref "C80") (pin "1") (pinfunction "1_1") (pintype "passive"))
      (node (ref "R29") (pin "1") (pinfunction "1_1") (pintype "passive"))
      (node (ref "R37") (pin "2") (pinfunction "2_2") (pintype "passive"))
      (node (ref "U6") (pin "32") (pinfunction "AIN10_32") (pintype "passive"))
    )
    (net (code "42") (name "Net-(U6-AIN11)") (class "Default")
      (node (ref "C80") (pin "2") (pinfunction "2_2") (pintype "passive"))
      (node (ref "C81") (pin "1") (pinfunction "1_1") (pintype "passive"))
      (node (ref "R43") (pin "1") (pinfunction "1_1") (pintype "passive"))
      (node (ref "R46") (pin "2") (pinfunction "2_2") (pintype "passive"))
      (node (ref "U6") (pin "33") (pinfunction "AIN11_33") (pintype "passive"))
    )
    (net (code "43") (name "Net-(U6-AIN12)") (class "Default")
      (node (ref "C84") (pin "1") (pinfunction "1_1") (pintype "passive"))
      (node (ref "C85") (pin "1") (pinfunction "1_1") (pintype "passive"))
      (node (ref "R30") (pin "1") (pinfunction "1_1") (pintype "passive"))
      (node (ref "R47") (pin "2") (pinfunction "2_2") (pintype "passive"))
      (node (ref "U6") (pin "34") (pinfunction "AIN12_34") (pintype "passive"))
    )
    (net (code "44") (name "Net-(U6-AIN13)") (class "Default")
      (node (ref "C85") (pin "2") (pinfunction "2_2") (pintype "passive"))
      (node (ref "C86") (pin "1") (pinfunction "1_1") (pintype "passive"))
      (node (ref "R44") (pin "1") (pinfunction "1_1") (pintype "passive"))
      (node (ref "R48") (pin "2") (pinfunction "2_2") (pintype "passive"))
      (node (ref "U6") (pin "35") (pinfunction "AIN13_35") (pintype "passive"))
    )
    (net (code "45") (name "Net-(U6-REGCAPA)") (class "Default")
      (node (ref "C71") (pin "1") (pinfunction "1_1") (pintype "passive"))
      (node (ref "C72") (pin "1") (pinfunction "1_1") (pintype "passive"))
      (node (ref "U6") (pin "7") (pinfunction "REGCAPA_7") (pintype "passive"))
    )
    (net (code "46") (name "Net-(U6-REGCAPD)") (class "Default")
      (node (ref "C73") (pin "1") (pinfunction "1_1") (pintype "passive"))
      (node (ref "C74") (pin "1") (pinfunction "1_1") (pintype "passive"))
      (node (ref "U6") (pin "22") (pinfunction "REGCAPD_22") (pintype "passive"))
    )
    (net (code "47") (name "unconnected-(U6-AIN16-Pad1)") (class "Default")
      (node (ref "U6") (pin "1") (pinfunction "AIN16_1") (pintype "passive+no_connect"))
    )
    (net (code "48") (name "unconnected-(U6-GPIO0-Pad23)") (class "Default")
      (node (ref "U6") (pin "23") (pinfunction "GPIO0_23") (pintype "bidirectional+no_connect"))
    )
    (net (code "49") (name "unconnected-(U6-GPIO1-Pad24)") (class "Default")
      (node (ref "U6") (pin "24") (pinfunction "GPIO1_24") (pintype "bidirectional+no_connect"))
    )
    (net (code "50") (name "unconnected-(U6-GPO2-Pad25)") (class "Default")
      (node (ref "U6") (pin "25") (pinfunction "GPO2_25") (pintype "output+no_connect"))
    )
    (net (code "51") (name "unconnected-(U6-GPO3-Pad38)") (class "Default")
      (node (ref "U6") (pin "38") (pinfunction "GPO3_38") (pintype "output+no_connect"))
    )
    (net (code "52") (name "unconnected-(U6-PDSW-Pad11)") (class "Default")
      (node (ref "U6") (pin "11") (pinfunction "PDSW_11") (pintype "passive+no_connect"))
    )
    (net (code "53") (name "unconnected-(U6-XTAL1-Pad12)") (class "Default")
      (node (ref "U6") (pin "12") (pinfunction "XTAL1_12") (pintype "input+no_connect"))
    )
    (net (code "54") (name "unconnected-(U6-XTAL2{slash}CLKIO-Pad13)") (class "Default")
      (node (ref "U6") (pin "13") (pinfunction "XTAL2/CLKIO_13") (pintype "bidirectional+no_connect"))
    )
    (net (code "55") (name "unconnected-(U6-~{ERROR}-Pad18)") (class "Default")
      (node (ref "U6") (pin "18") (pinfunction "~{ERROR}_18") (pintype "output+no_connect"))
    )
    (net (code "56") (name "unconnected-(U6-~{SYNC}-Pad19)") (class "Default")
      (node (ref "U6") (pin "19") (pinfunction "~{SYNC}_19") (pintype "input+no_connect"))
    )
  )
)
